# TSL230RD_breakout.net
KiCad netlist of a schematic drawn in EAGLE
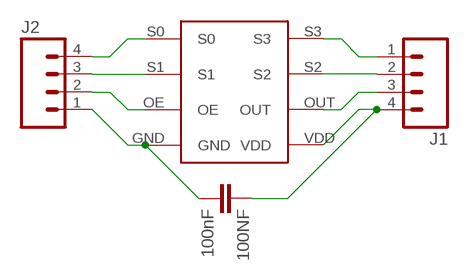
[diagram p0: schematic, sheet 1]

(export (version "E")
  (design (tool "Eeschema 10.0.6"))
  (components
    (comp (ref "100NF")
      (value "100nF")
      (footprint "eagle-import:0603-CAP")
      (libsource (lib "eagle-import") (part "CAP0603-CAP"))
    )
    (comp (ref "J1")
      (value "M04PTH")
      (footprint "eagle-import:1X04")
      (libsource (lib "eagle-import") (part "M04PTH"))
    )
    (comp (ref "J2")
      (value "M04PTH")
      (footprint "eagle-import:1X04")
      (libsource (lib "eagle-import") (part "M04PTH"))
    )
    (comp (ref "U$1")
      (value "TSL230RDSMD")
      (footprint "eagle-import:TSL230RD")
      (libsource (lib "eagle-import") (part "TSL230RDSMD"))
    )
  )
  (nets
    (net (code "1") (name "Net-(100NF-Pad1)") (class "Default")
      (node (ref "100NF") (pin "1") (pinfunction "1_1") (pintype "passive"))
      (node (ref "J1") (pin "4") (pinfunction "4_4") (pintype "passive"))
      (node (ref "U$1") (pin "VDD") (pinfunction "VDD_VDD") (pintype "bidirectional"))
    )
    (net (code "2") (name "Net-(100NF-Pad2)") (class "Default")
      (node (ref "100NF") (pin "2") (pinfunction "2_2") (pintype "passive"))
      (node (ref "J2") (pin "1") (pinfunction "1_1") (pintype "passive"))
      (node (ref "U$1") (pin "GND") (pinfunction "GND_GND") (pintype "bidirectional"))
    )
    (net (code "3") (name "Net-(J1-Pad1)") (class "Default")
      (node (ref "J1") (pin "1") (pinfunction "1_1") (pintype "passive"))
      (node (ref "U$1") (pin "S3") (pinfunction "S3_S3") (pintype "bidirectional"))
    )
    (net (code "4") (name "Net-(J1-Pad2)") (class "Default")
      (node (ref "J1") (pin "2") (pinfunction "2_2") (pintype "passive"))
      (node (ref "U$1") (pin "S2") (pinfunction "S2_S2") (pintype "bidirectional"))
    )
    (net (code "5") (name "Net-(J1-Pad3)") (class "Default")
      (node (ref "J1") (pin "3") (pinfunction "3_3") (pintype "passive"))
      (node (ref "U$1") (pin "OUT") (pinfunction "OUT_OUT") (pintype "bidirectional"))
    )
    (net (code "6") (name "Net-(J2-Pad2)") (class "Default")
      (node (ref "J2") (pin "2") (pinfunction "2_2") (pintype "passive"))
      (node (ref "U$1") (pin "OE") (pinfunction "OE_OE") (pintype "bidirectional"))
    )
    (net (code "7") (name "Net-(J2-Pad3)") (class "Default")
      (node (ref "J2") (pin "3") (pinfunction "3_3") (pintype "passive"))
      (node (ref "U$1") (pin "S1") (pinfunction "S1_S1") (pintype "bidirectional"))
    )
    (net (code "8") (name "Net-(J2-Pad4)") (class "Default")
      (node (ref "J2") (pin "4") (pinfunction "4_4") (pintype "passive"))
      (node (ref "U$1") (pin "S0") (pinfunction "S0_S0") (pintype "bidirectional"))
    )
  )
)
